# schematic.net
KiCad netlist of a schematic drawn in EasyEDA
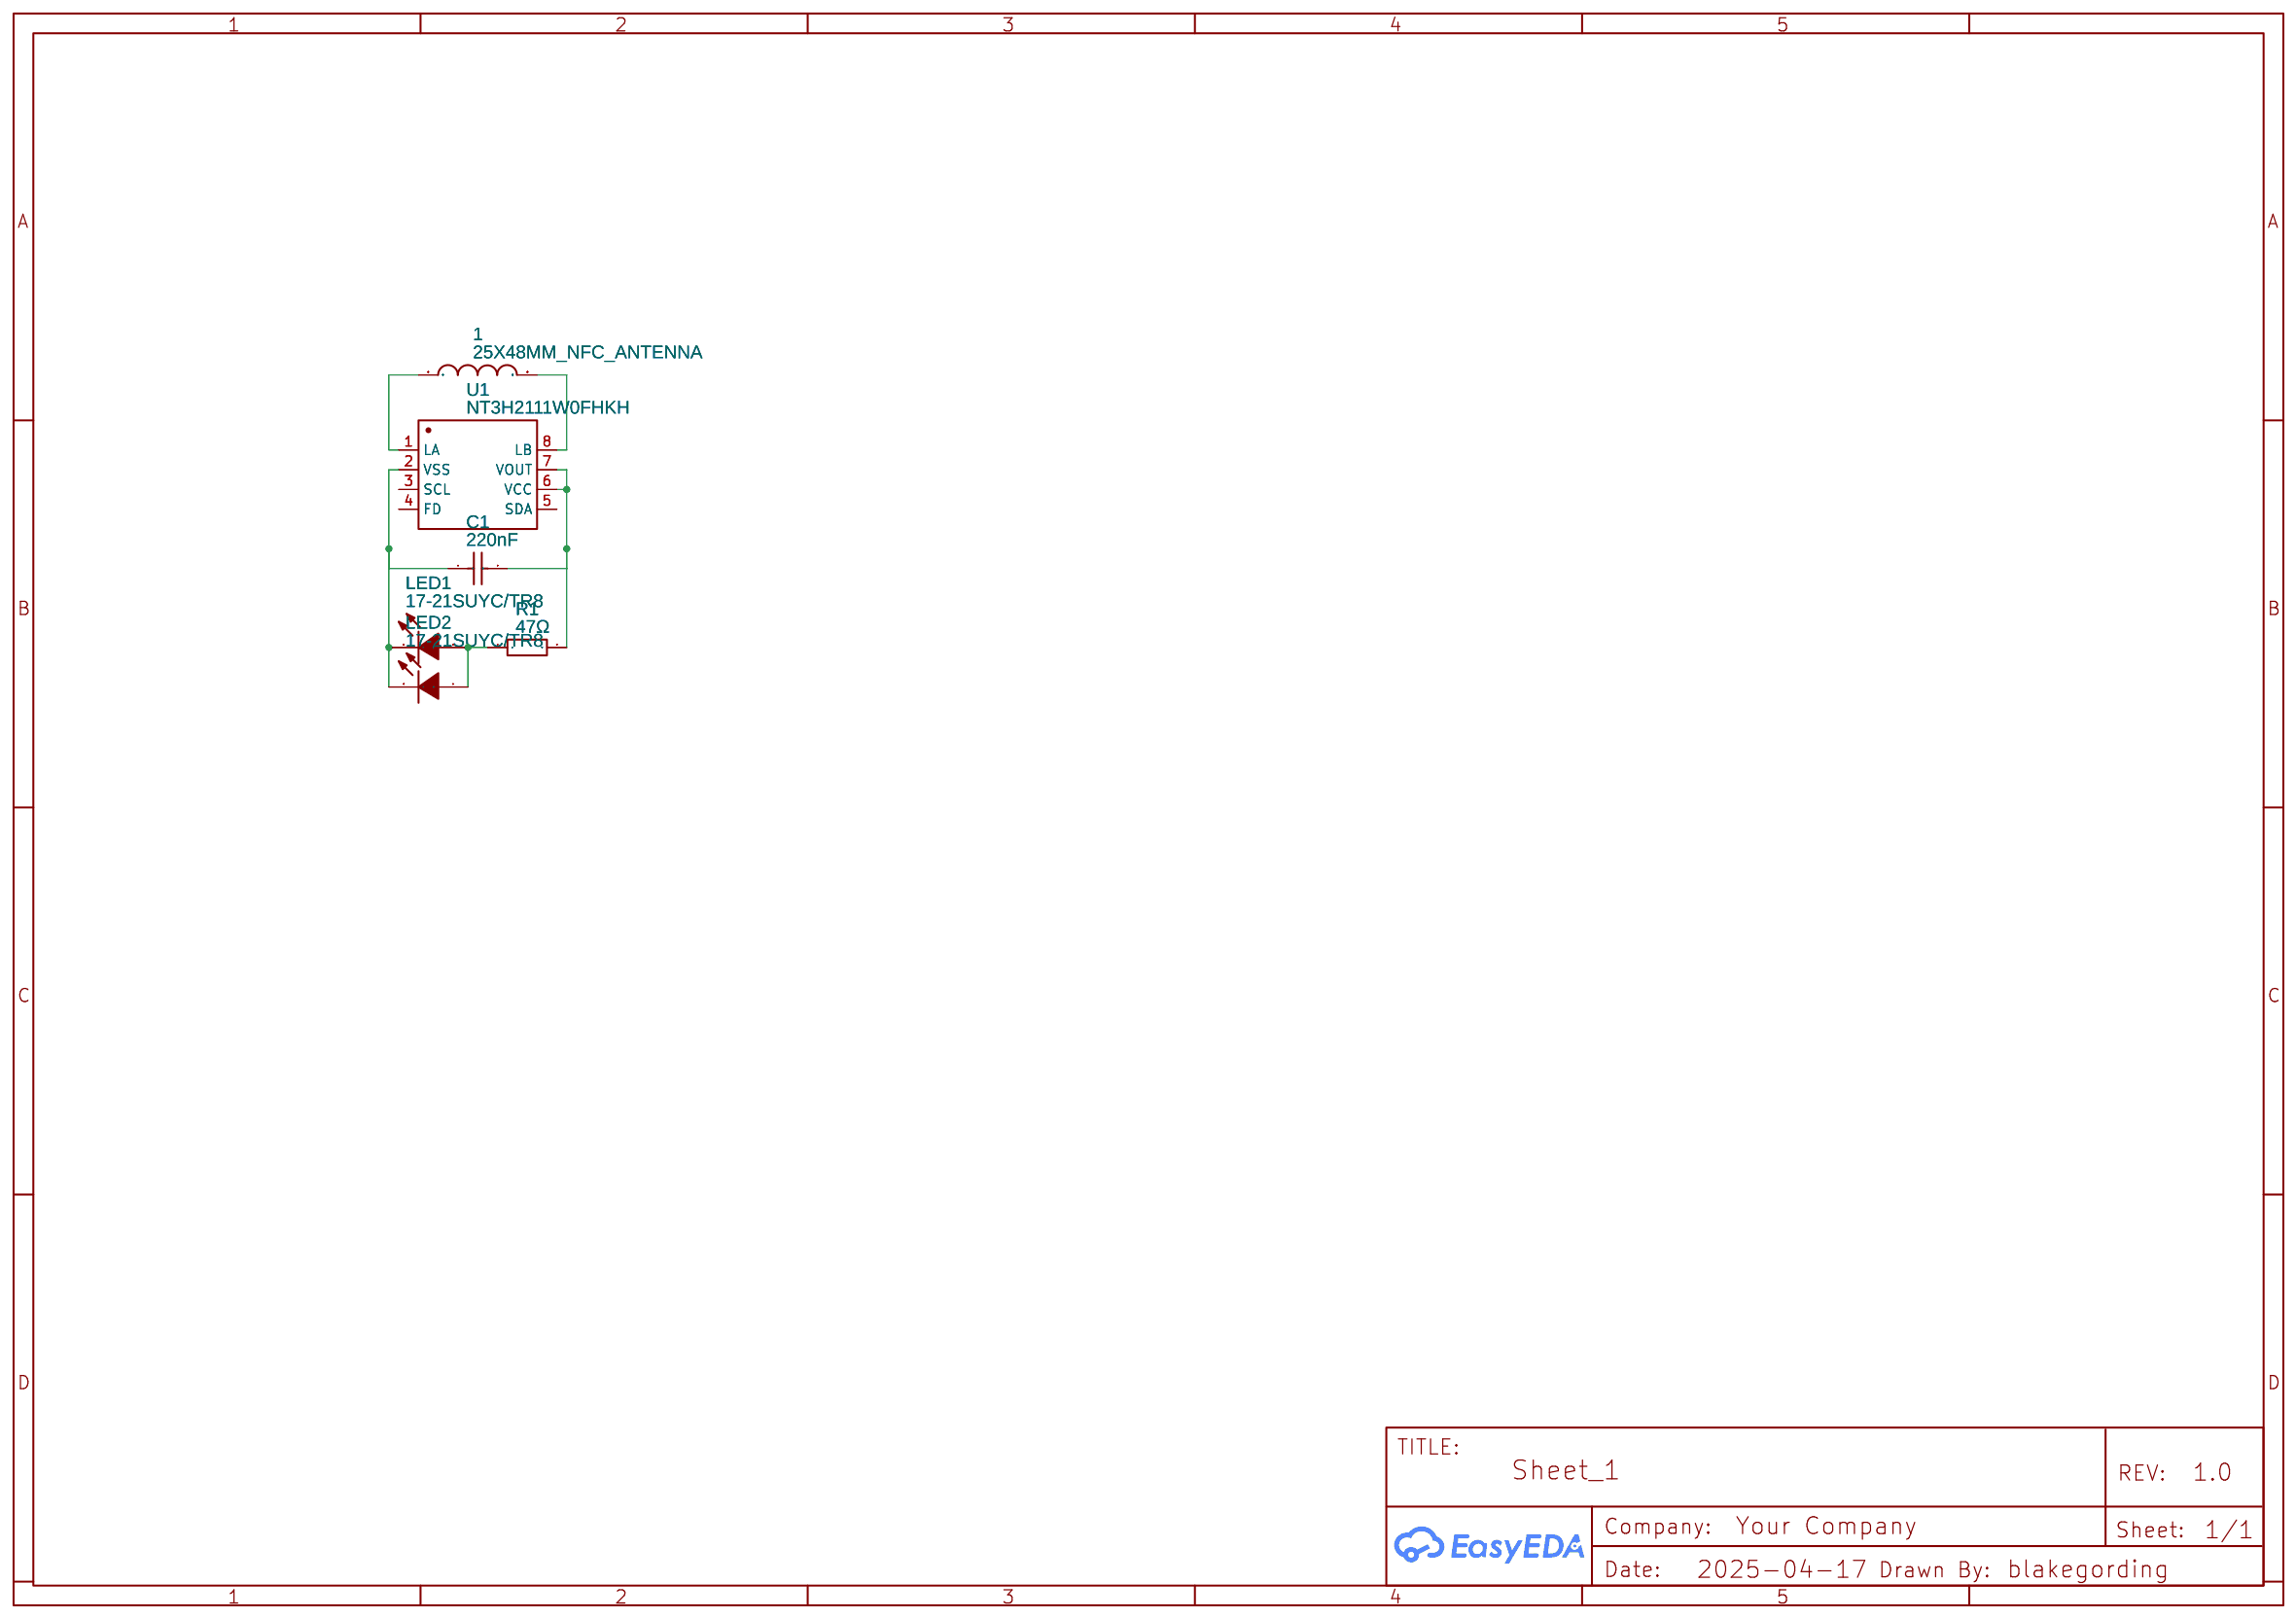
[diagram p0: schematic sheet]

(export (version "E")
  (design (tool "Eeschema 10.0.6"))
  (components
    (comp (ref "1") (value "25X48MM_NFC_ANTENNA") (libsource (lib "") (part "25X48MM_NFC_ANTENNA")))
    (comp (ref "C1")
      (value "220nF")
      (fields
        (field (name "Manufacturer Part") "CL10B224KA8NNNC")
        (field (name "Manufacturer") "SAMSUNG(三星)")
      )
      (libsource (lib "") (part "CL10B224KA8NNNC"))
    )
    (comp (ref "LED1")
      (value "17-21SUYC/TR8")
      (fields (field (name "Manufacturer Part") "KT-0805黄灯") (field (name "Manufacturer") "KENTO"))
      (libsource (lib "") (part "17-21SUYC/TR8"))
    )
    (comp (ref "LED2")
      (value "17-21SUYC/TR8")
      (fields (field (name "Manufacturer Part") "KT-0805黄灯") (field (name "Manufacturer") "KENTO"))
      (libsource (lib "") (part "17-21SUYC/TR8"))
    )
    (comp (ref "R1")
      (value "47Ω")
      (fields
        (field (name "Manufacturer Part") "0603WAF470JT5E")
        (field (name "Manufacturer") "UNI-ROYAL(厚声)")
      )
      (libsource (lib "") (part "0603WAF470JT5E"))
    )
    (comp (ref "U1")
      (value "NT3H2111W0FHKH")
      (fields (field (name "Manufacturer") "NXP(恩智浦)"))
      (libsource (lib "") (part "NT3H2111W0FHKH"))
    )
  )
  (nets
    (net (code "1") (name "Net-(LED1-+)") (class "Default")
      (node (ref "LED1") (pin "1") (pinfunction "+_1") (pintype "unspecified"))
      (node (ref "LED2") (pin "1") (pinfunction "+_1") (pintype "unspecified"))
      (node (ref "R1") (pin "1") (pinfunction "1_1") (pintype "input"))
    )
    (net (code "2") (name "Net-(LED1--)") (class "Default")
      (node (ref "C1") (pin "1") (pinfunction "1_1") (pintype "input"))
      (node (ref "LED1") (pin "2") (pinfunction "-_2") (pintype "unspecified"))
      (node (ref "LED2") (pin "2") (pinfunction "-_2") (pintype "unspecified"))
      (node (ref "U1") (pin "2") (pinfunction "VSS_2") (pintype "unspecified"))
    )
    (net (code "3") (name "Net-(U1-LA)") (class "Default")
      (node (ref "1") (pin "P$1") (pinfunction "P$1_P$1") (pintype "bidirectional"))
      (node (ref "U1") (pin "1") (pinfunction "LA_1") (pintype "unspecified"))
    )
    (net (code "4") (name "Net-(U1-LB)") (class "Default")
      (node (ref "1") (pin "P$2") (pinfunction "P$2_P$2") (pintype "bidirectional"))
      (node (ref "U1") (pin "8") (pinfunction "LB_8") (pintype "unspecified"))
    )
    (net (code "5") (name "Net-(U1-VCC)") (class "Default")
      (node (ref "C1") (pin "2") (pinfunction "2_2") (pintype "input"))
      (node (ref "R1") (pin "2") (pinfunction "2_2") (pintype "input"))
      (node (ref "U1") (pin "6") (pinfunction "VCC_6") (pintype "unspecified"))
      (node (ref "U1") (pin "7") (pinfunction "VOUT_7") (pintype "unspecified"))
    )
    (net (code "6") (name "unconnected-(U1-FD-Pad4)") (class "Default")
      (node (ref "U1") (pin "4") (pinfunction "FD_4") (pintype "unspecified"))
    )
    (net (code "7") (name "unconnected-(U1-SCL-Pad3)") (class "Default")
      (node (ref "U1") (pin "3") (pinfunction "SCL_3") (pintype "unspecified"))
    )
    (net (code "8") (name "unconnected-(U1-SDA-Pad5)") (class "Default")
      (node (ref "U1") (pin "5") (pinfunction "SDA_5") (pintype "unspecified"))
    )
  )
)
